# ScoutMakes_FM_StemmaQT.net
KiCad netlist of a schematic drawn in EAGLE
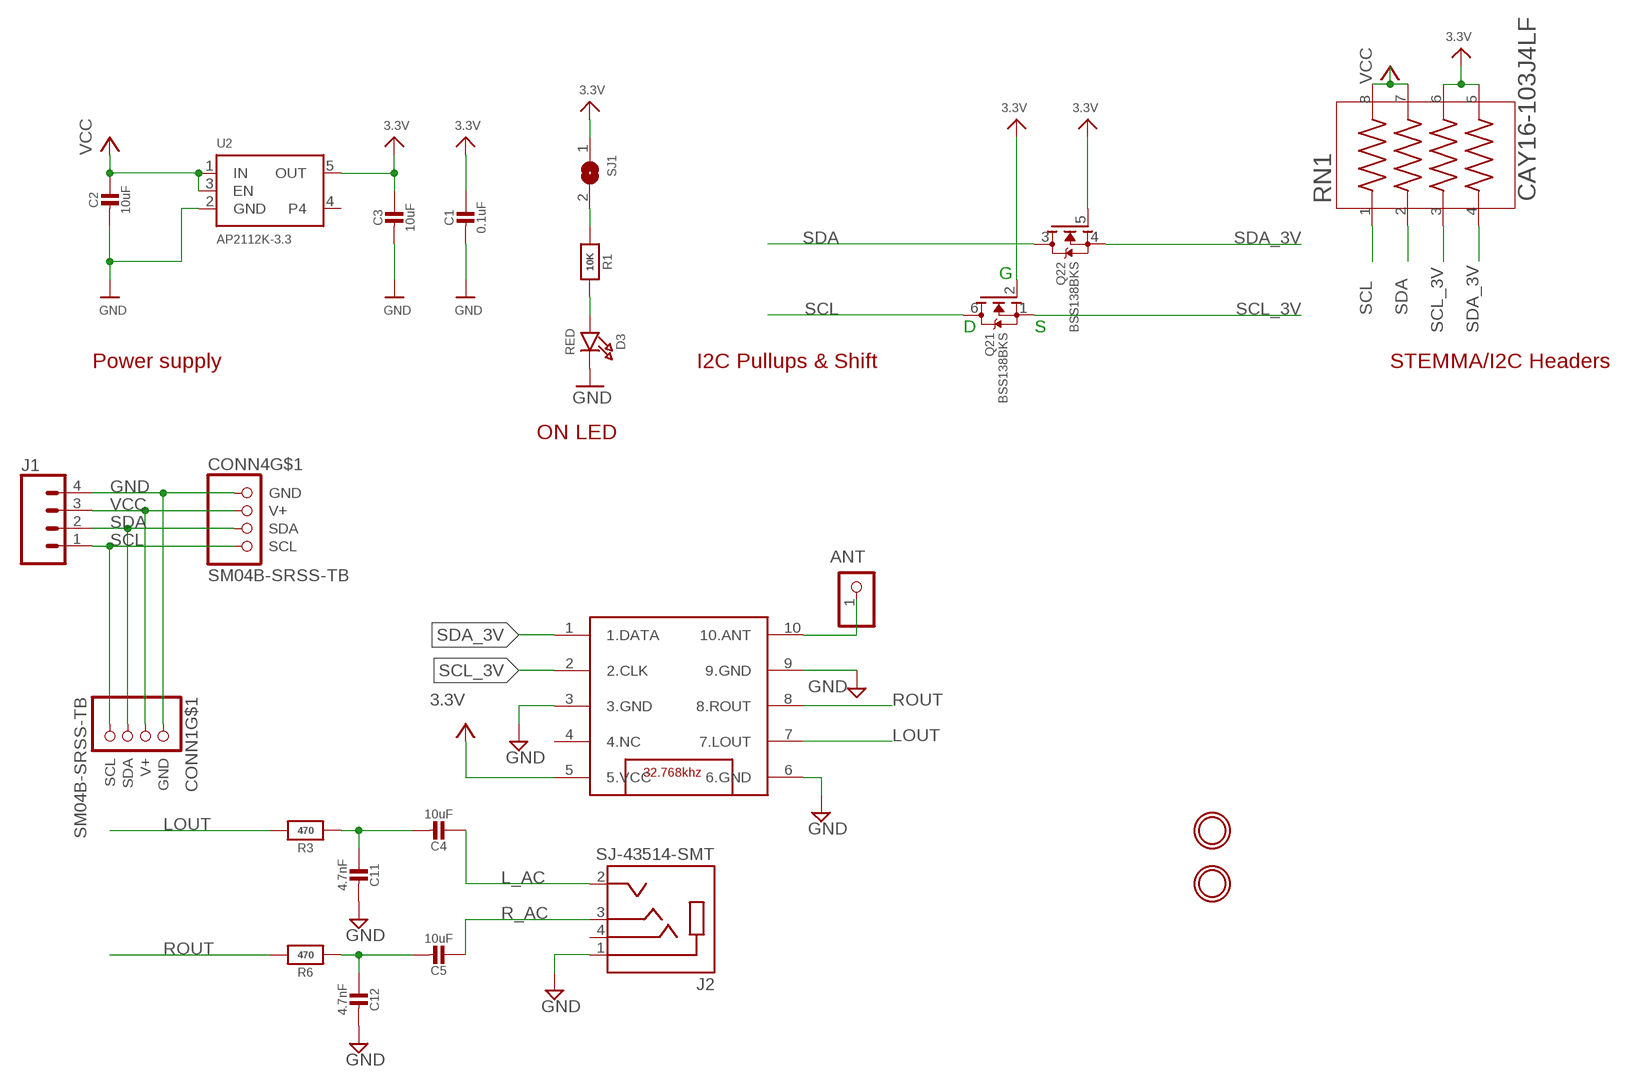
[diagram p0: schematic, sheet 1]

(export (version "E")
  (design (tool "Eeschema 10.0.6"))
  (components
    (comp (ref "ANT")
      (value "PINHD-1X1")
      (footprint "eagle-import:1X01")
      (libsource (lib "eagle-import") (part "PINHD-1X1"))
    )
    (comp (ref "C1")
      (value "0.1uF")
      (footprint "eagle-import:0603-NO")
      (libsource (lib "eagle-import") (part "CAP_CERAMIC0603_NO"))
    )
    (comp (ref "C2")
      (value "10uF")
      (footprint "eagle-import:0805-NO")
      (libsource (lib "eagle-import") (part "CAP_CERAMIC0805-NOOUTLINE"))
    )
    (comp (ref "C3")
      (value "10uF")
      (footprint "eagle-import:0805-NO")
      (libsource (lib "eagle-import") (part "CAP_CERAMIC0805-NOOUTLINE"))
    )
    (comp (ref "C4")
      (value "10uF")
      (footprint "eagle-import:0805-NO")
      (libsource (lib "eagle-import") (part "CAP_CERAMIC0805-NOOUTLINE"))
    )
    (comp (ref "C5")
      (value "10uF")
      (footprint "eagle-import:0805-NO")
      (libsource (lib "eagle-import") (part "CAP_CERAMIC0805-NOOUTLINE"))
    )
    (comp (ref "C11")
      (value "4.7nF")
      (footprint "eagle-import:0805-NO")
      (libsource (lib "eagle-import") (part "CAP_CERAMIC0805-NOOUTLINE"))
    )
    (comp (ref "C12")
      (value "4.7nF")
      (footprint "eagle-import:0805-NO")
      (libsource (lib "eagle-import") (part "CAP_CERAMIC0805-NOOUTLINE"))
    )
    (comp (ref "CONN1")
      (value "SM04B-SRSS-TB")
      (footprint "eagle-import:JST_SH4")
      (libsource (lib "eagle-import") (part "STEMMA_I2C_QT"))
    )
    (comp (ref "CONN4")
      (value "SM04B-SRSS-TB")
      (footprint "eagle-import:JST_SH4")
      (libsource (lib "eagle-import") (part "STEMMA_I2C_QT"))
    )
    (comp (ref "D3")
      (value "RED")
      (footprint "eagle-import:CHIPLED_0805_NOOUTLINE")
      (libsource (lib "eagle-import") (part "LED0805_NOOUTLINE"))
    )
    (comp (ref "J1")
      (value "CONN_04")
      (footprint "eagle-import:1X04")
      (libsource (lib "eagle-import") (part "CONN_04"))
    )
    (comp (ref "J2")
      (value "SJ-43514-SMT")
      (footprint "eagle-import:CUI_SJ-43514-SMT")
      (fields
        (field (name "DIGI-KEY_PART_NUMBER") "CP-43514SJCT-ND")
        (field (name "MF") "CUI Devices")
        (field (name "MP") "SJ-43514-SMT-TR")
      )
      (libsource (lib "eagle-import") (part "SJ-43514-SMT"))
    )
    (comp (ref "Q2")
      (value "BSS138BKS")
      (footprint "eagle-import:SOT363")
      (libsource (lib "eagle-import") (part "MOSFET-N_DUAL"))
    )
    (comp (ref "R1")
      (value "10K")
      (footprint "eagle-import:0603-NO")
      (libsource (lib "eagle-import") (part "RESISTOR_0603_NOOUT"))
    )
    (comp (ref "R3")
      (value "470")
      (footprint "eagle-import:0805-NO")
      (libsource (lib "eagle-import") (part "RESISTOR0805_NOOUTLINE"))
    )
    (comp (ref "R6")
      (value "470")
      (footprint "eagle-import:0805-NO")
      (libsource (lib "eagle-import") (part "RESISTOR0805_NOOUTLINE"))
    )
    (comp (ref "RN1")
      (value "CAY16-103J4LF")
      (footprint "eagle-import:RESCAF80P320X160X60-8N")
      (fields (field (name "DIGI-KEY_PART_NUMBER") "CAY16-103J4LFCT-ND") (field (name "MF") "Bourns"))
      (libsource (lib "eagle-import") (part "CAY16-103J4LF"))
    )
    (comp (ref "SJ1")
      (value "SOLDERJUMPER")
      (footprint "eagle-import:SOLDERJUMPER_ARROW_NOPASTE")
      (libsource (lib "eagle-import") (part "SOLDERJUMPER"))
    )
    (comp (ref "U$1")
      (value "MOUNTINGHOLE2.5")
      (footprint "eagle-import:MOUNTINGHOLE_2.5_PLATED")
      (libsource (lib "eagle-import") (part "MOUNTINGHOLE2.5"))
    )
    (comp (ref "U$17")
      (value "MOUNTINGHOLE2.5")
      (footprint "eagle-import:MOUNTINGHOLE_2.5_PLATED")
      (libsource (lib "eagle-import") (part "MOUNTINGHOLE2.5"))
    )
    (comp (ref "U1")
      (value "TEA5767")
      (footprint "eagle-import:TJ-102BC")
      (libsource (lib "eagle-import") (part "TEA5767"))
    )
    (comp (ref "U2")
      (value "AP2112K-3.3")
      (footprint "eagle-import:SOT23-5")
      (libsource (lib "eagle-import") (part "VREG_SOT23-5"))
    )
  )
  (nets
    (net (code "1") (name "/LOUT") (class "Default")
      (node (ref "R3") (pin "1") (pinfunction "1_1") (pintype "passive"))
      (node (ref "U1") (pin "7") (pinfunction "7.LOUT_7") (pintype "bidirectional"))
    )
    (net (code "2") (name "/L_AC") (class "Default")
      (node (ref "C4") (pin "1") (pinfunction "1_1") (pintype "passive"))
      (node (ref "J2") (pin "2") (pinfunction "TIP_2") (pintype "passive"))
    )
    (net (code "3") (name "/ROUT") (class "Default")
      (node (ref "R6") (pin "1") (pinfunction "1_1") (pintype "passive"))
      (node (ref "U1") (pin "8") (pinfunction "8.ROUT_8") (pintype "bidirectional"))
    )
    (net (code "4") (name "/R_AC") (class "Default")
      (node (ref "C5") (pin "1") (pinfunction "1_1") (pintype "passive"))
      (node (ref "J2") (pin "3") (pinfunction "RING1_3") (pintype "passive"))
    )
    (net (code "5") (name "/SCL") (class "Default")
      (node (ref "CONN1") (pin "4") (pinfunction "SCL_4") (pintype "passive"))
      (node (ref "CONN4") (pin "4") (pinfunction "SCL_4") (pintype "passive"))
      (node (ref "J1") (pin "1") (pinfunction "1_1") (pintype "passive"))
      (node (ref "Q2") (pin "6") (pinfunction "D_6") (pintype "bidirectional"))
      (node (ref "RN1") (pin "1") (pinfunction "1_1") (pintype "passive"))
    )
    (net (code "6") (name "/SDA") (class "Default")
      (node (ref "CONN1") (pin "3") (pinfunction "SDA_3") (pintype "passive"))
      (node (ref "CONN4") (pin "3") (pinfunction "SDA_3") (pintype "passive"))
      (node (ref "J1") (pin "2") (pinfunction "2_2") (pintype "passive"))
      (node (ref "Q2") (pin "3") (pinfunction "D_3") (pintype "bidirectional"))
      (node (ref "RN1") (pin "2") (pinfunction "2_2") (pintype "passive"))
    )
    (net (code "7") (name "3.3V") (class "Default")
      (node (ref "C1") (pin "1") (pinfunction "1_1") (pintype "passive"))
      (node (ref "C3") (pin "1") (pinfunction "1_1") (pintype "passive"))
      (node (ref "Q2") (pin "2") (pinfunction "G_2") (pintype "bidirectional"))
      (node (ref "Q2") (pin "5") (pinfunction "G_5") (pintype "bidirectional"))
      (node (ref "RN1") (pin "5") (pinfunction "5_5") (pintype "passive"))
      (node (ref "RN1") (pin "6") (pinfunction "6_6") (pintype "passive"))
      (node (ref "SJ1") (pin "1") (pinfunction "1_1") (pintype "passive"))
      (node (ref "U1") (pin "5") (pinfunction "5.VCC_5") (pintype "bidirectional"))
      (node (ref "U2") (pin "5") (pinfunction "OUT_5") (pintype "power_in"))
    )
    (net (code "8") (name "GND") (class "Default")
      (node (ref "C1") (pin "2") (pinfunction "2_2") (pintype "passive"))
      (node (ref "C11") (pin "2") (pinfunction "2_2") (pintype "passive"))
      (node (ref "C12") (pin "2") (pinfunction "2_2") (pintype "passive"))
      (node (ref "C2") (pin "2") (pinfunction "2_2") (pintype "passive"))
      (node (ref "C3") (pin "2") (pinfunction "2_2") (pintype "passive"))
      (node (ref "CONN1") (pin "1") (pinfunction "GND_1") (pintype "passive"))
      (node (ref "CONN4") (pin "1") (pinfunction "GND_1") (pintype "passive"))
      (node (ref "D3") (pin "C") (pinfunction "C_C") (pintype "passive"))
      (node (ref "J1") (pin "4") (pinfunction "4_4") (pintype "passive"))
      (node (ref "J2") (pin "1") (pinfunction "SLEEVE_1") (pintype "passive"))
      (node (ref "U1") (pin "3") (pinfunction "3.GND_3") (pintype "bidirectional"))
      (node (ref "U1") (pin "6") (pinfunction "6.GND_6") (pintype "bidirectional"))
      (node (ref "U1") (pin "9") (pinfunction "9.GND_9") (pintype "bidirectional"))
      (node (ref "U2") (pin "2") (pinfunction "GND_2") (pintype "power_in"))
    )
    (net (code "9") (name "Net-(C11-Pad1)") (class "Default")
      (node (ref "C11") (pin "1") (pinfunction "1_1") (pintype "passive"))
      (node (ref "C4") (pin "2") (pinfunction "2_2") (pintype "passive"))
      (node (ref "R3") (pin "2") (pinfunction "2_2") (pintype "passive"))
    )
    (net (code "10") (name "Net-(C12-Pad1)") (class "Default")
      (node (ref "C12") (pin "1") (pinfunction "1_1") (pintype "passive"))
      (node (ref "C5") (pin "2") (pinfunction "2_2") (pintype "passive"))
      (node (ref "R6") (pin "2") (pinfunction "2_2") (pintype "passive"))
    )
    (net (code "11") (name "Net-(D3-PadA)") (class "Default")
      (node (ref "D3") (pin "A") (pinfunction "A_A") (pintype "passive"))
      (node (ref "R1") (pin "2") (pinfunction "2_2") (pintype "passive"))
    )
    (net (code "12") (name "Net-(R1-Pad1)") (class "Default")
      (node (ref "R1") (pin "1") (pinfunction "1_1") (pintype "passive"))
      (node (ref "SJ1") (pin "2") (pinfunction "2_2") (pintype "passive"))
    )
    (net (code "13") (name "Net-(U1-10.ANT)") (class "Default")
      (node (ref "ANT") (pin "1") (pinfunction "1_1") (pintype "passive"))
      (node (ref "U1") (pin "10") (pinfunction "10.ANT_10") (pintype "bidirectional"))
    )
    (net (code "14") (name "SCL_3V") (class "Default")
      (node (ref "Q2") (pin "1") (pinfunction "S_1") (pintype "bidirectional"))
      (node (ref "RN1") (pin "3") (pinfunction "3_3") (pintype "passive"))
      (node (ref "U1") (pin "2") (pinfunction "2.CLK_2") (pintype "bidirectional"))
    )
    (net (code "15") (name "SDA_3V") (class "Default")
      (node (ref "Q2") (pin "4") (pinfunction "S_4") (pintype "bidirectional"))
      (node (ref "RN1") (pin "4") (pinfunction "4_4") (pintype "passive"))
      (node (ref "U1") (pin "1") (pinfunction "1.DATA_1") (pintype "bidirectional"))
    )
    (net (code "16") (name "VCC") (class "Default")
      (node (ref "C2") (pin "1") (pinfunction "1_1") (pintype "passive"))
      (node (ref "CONN1") (pin "2") (pinfunction "V+_2") (pintype "passive"))
      (node (ref "CONN4") (pin "2") (pinfunction "V+_2") (pintype "passive"))
      (node (ref "J1") (pin "3") (pinfunction "3_3") (pintype "passive"))
      (node (ref "RN1") (pin "7") (pinfunction "7_7") (pintype "passive"))
      (node (ref "RN1") (pin "8") (pinfunction "8_8") (pintype "passive"))
      (node (ref "U2") (pin "1") (pinfunction "IN_1") (pintype "power_in"))
      (node (ref "U2") (pin "3") (pinfunction "EN_3") (pintype "input"))
    )
    (net (code "17") (name "unconnected-(J2-RING2-Pad4)") (class "Default")
      (node (ref "J2") (pin "4") (pinfunction "RING2_4") (pintype "passive"))
    )
    (net (code "18") (name "unconnected-(U1-4.NC-Pad4)") (class "Default")
      (node (ref "U1") (pin "4") (pinfunction "4.NC_4") (pintype "bidirectional"))
    )
    (net (code "19") (name "unconnected-(U2-P4-Pad4)") (class "Default")
      (node (ref "U2") (pin "4") (pinfunction "P4_4") (pintype "bidirectional"))
    )
  )
)
